# main.net
KiCad netlist of a schematic drawn in Altium Designer
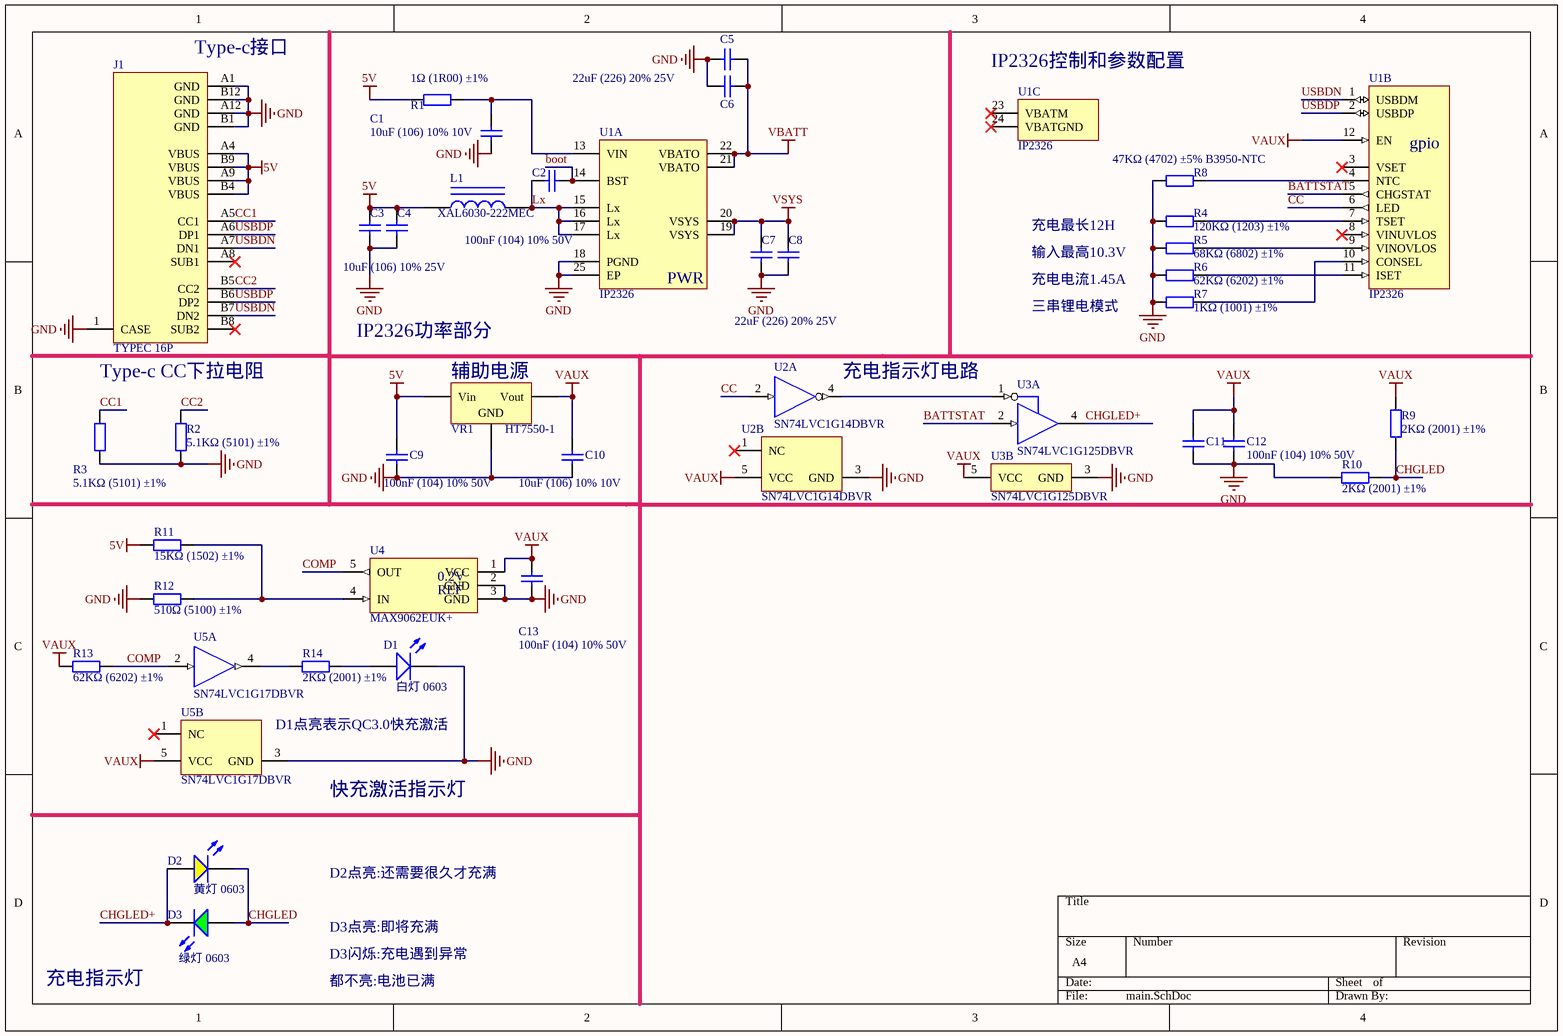
[diagram p0: main.SchDoc]

(export (version "E")
  (design (tool "Eeschema 10.0.6"))
  (components
    (comp (ref "C1")
      (value "10uF (106) 10% 10V")
      (footprint "0603_C")
      (description "贴片电容")
      (libsource (lib "Miscellaneous Devices LC") (part "0603 10uF (106) 10% 10V"))
    )
    (comp (ref "C2")
      (value "100nF (104) 10% 50V")
      (footprint "0603_C")
      (description "贴片电容")
      (libsource (lib "Miscellaneous Devices LC") (part "0603 100nF (104) 10% 50V"))
    )
    (comp (ref "C3")
      (value "10uF (106) 10% 25V")
      (footprint "0805_C")
      (description "贴片电容")
      (libsource (lib "Miscellaneous Devices LC") (part "0805 10uF (106) 10% 25V"))
    )
    (comp (ref "C4")
      (value "10uF (106) 10% 25V")
      (footprint "0805_C")
      (description "贴片电容")
      (libsource (lib "Miscellaneous Devices LC") (part "0805 10uF (106) 10% 25V"))
    )
    (comp (ref "C5")
      (value "22uF (226) 20% 25V")
      (footprint "0805_C")
      (description "贴片电容")
      (libsource (lib "Miscellaneous Devices LC") (part "0805 22uF (226) 20% 25V"))
    )
    (comp (ref "C6")
      (value "22uF (226) 20% 25V")
      (footprint "0805_C")
      (description "贴片电容")
      (libsource (lib "Miscellaneous Devices LC") (part "0805 22uF (226) 20% 25V"))
    )
    (comp (ref "C7")
      (value "22uF (226) 20% 25V")
      (footprint "0805_C")
      (description "贴片电容")
      (libsource (lib "Miscellaneous Devices LC") (part "0805 22uF (226) 20% 25V"))
    )
    (comp (ref "C8")
      (value "22uF (226) 20% 25V")
      (footprint "0805_C")
      (description "贴片电容")
      (libsource (lib "Miscellaneous Devices LC") (part "0805 22uF (226) 20% 25V"))
    )
    (comp (ref "C9")
      (value "100nF (104) 10% 50V")
      (footprint "0603_C")
      (description "贴片电容")
      (libsource (lib "Miscellaneous Devices LC") (part "0603 100nF (104) 10% 50V"))
    )
    (comp (ref "C10")
      (value "10uF (106) 10% 10V")
      (footprint "0603_C")
      (description "贴片电容")
      (libsource (lib "Miscellaneous Devices LC") (part "0603 10uF (106) 10% 10V"))
    )
    (comp (ref "C11")
      (value "100nF (104) 10% 50V")
      (footprint "0603_C")
      (description "贴片电容")
      (libsource (lib "Miscellaneous Devices LC") (part "0603 100nF (104) 10% 50V"))
    )
    (comp (ref "C12")
      (value "100nF (104) 10% 50V")
      (footprint "0603_C")
      (description "贴片电容")
      (libsource (lib "Miscellaneous Devices LC") (part "0603 100nF (104) 10% 50V"))
    )
    (comp (ref "C13")
      (value "100nF (104) 10% 50V")
      (footprint "0603_C")
      (description "贴片电容")
      (libsource (lib "Miscellaneous Devices LC") (part "0603 100nF (104) 10% 50V"))
    )
    (comp (ref "D1")
      (value "白灯 0603")
      (footprint "0603_LED_S1")
      (description "发光二极管")
      (libsource (lib "Miscellaneous Devices LC") (part "0603 白灯"))
    )
    (comp (ref "D2")
      (value "黄灯 0603")
      (footprint "0603_LED_S1")
      (description "发光二极管")
      (libsource (lib "Miscellaneous Devices LC") (part "0603 黄灯"))
    )
    (comp (ref "D3")
      (value "绿灯 0603")
      (footprint "0603_LED_S1")
      (description "发光二极管")
      (libsource (lib "Miscellaneous Devices LC") (part "0603 绿灯"))
    )
    (comp (ref "J1")
      (value "TYPEC 16P")
      (footprint "USB-C-SMD_KH-TYPE-C-16P")
      (description "16Pin TypeC立贴座子")
      (libsource (lib "custom") (part "KH-TYPEC-16P"))
    )
    (comp (ref "L1")
      (value "XAL6030-222MEC")
      (footprint "XAL6030-xxxME")
      (description "Magnetic-Core Inductor")
      (fields (field (name "PUBLISHER") "Altium Limited"))
      (libsource (lib "Miscellaneous Devices") (part "Inductor Iron"))
    )
    (comp (ref "R1")
      (value "1Ω (1R00) ±1%")
      (footprint "0603_R")
      (description "贴片电阻")
      (libsource (lib "Miscellaneous Devices LC") (part "0603 1Ω (1R00) 1%"))
    )
    (comp (ref "R2")
      (value "5.1KΩ (5101) ±1%")
      (footprint "0603_R")
      (description "贴片电阻")
      (libsource (lib "Miscellaneous Devices LC") (part "0603 5.1KΩ (5101) 1%"))
    )
    (comp (ref "R3")
      (value "5.1KΩ (5101) ±1%")
      (footprint "0603_R")
      (description "贴片电阻")
      (libsource (lib "Miscellaneous Devices LC") (part "0603 5.1KΩ (5101) 1%"))
    )
    (comp (ref "R4")
      (value "120KΩ (1203) ±1%")
      (footprint "0603_R")
      (description "贴片电阻")
      (libsource (lib "Miscellaneous Devices LC") (part "0603 120KΩ (1203) 1%"))
    )
    (comp (ref "R5")
      (value "68KΩ (6802) ±1%")
      (footprint "0603_R")
      (description "贴片电阻")
      (libsource (lib "Miscellaneous Devices LC") (part "0603 68KΩ (6802) 1%"))
    )
    (comp (ref "R6")
      (value "62KΩ (6202) ±1%")
      (footprint "0603_R")
      (description "贴片电阻")
      (libsource (lib "Miscellaneous Devices LC") (part "0603 62KΩ (6202) 1%"))
    )
    (comp (ref "R7")
      (value "1KΩ (1001) ±1%")
      (footprint "0603_R")
      (description "贴片电阻")
      (libsource (lib "Miscellaneous Devices LC") (part "0603 1KΩ (1001) 1%"))
    )
    (comp (ref "R8")
      (value "47KΩ (4702) ±5% B3950-NTC")
      (footprint "0603_R")
      (description "贴片NTC热敏电阻")
      (libsource (lib "Miscellaneous Devices LC") (part "0603 100KΩ (1003) 1%"))
    )
    (comp (ref "R9")
      (value "2KΩ (2001) ±1%")
      (footprint "0603_R")
      (description "贴片电阻")
      (libsource (lib "Miscellaneous Devices LC") (part "0603 2KΩ (2001) 1%"))
    )
    (comp (ref "R10")
      (value "2KΩ (2001) ±1%")
      (footprint "0603_R")
      (description "贴片电阻")
      (libsource (lib "") (part "0603 2KΩ (2001) 1%_1"))
    )
    (comp (ref "R11")
      (value "15KΩ (1502) ±1%")
      (footprint "0603_R")
      (description "贴片电阻")
      (libsource (lib "Miscellaneous Devices LC") (part "0603 15KΩ (1502) 1%"))
    )
    (comp (ref "R12")
      (value "510Ω (5100) ±1%")
      (footprint "0603_R")
      (description "贴片电阻")
      (libsource (lib "Miscellaneous Devices LC") (part "0603 510Ω (5100) 1%"))
    )
    (comp (ref "R13")
      (value "62KΩ (6202) ±1%")
      (footprint "0603_R")
      (description "贴片电阻")
      (libsource (lib "") (part "0603 62KΩ (6202) 1%_1"))
    )
    (comp (ref "R14")
      (value "2KΩ (2001) ±1%")
      (footprint "0603_R")
      (description "贴片电阻")
      (libsource (lib "") (part "0603 2KΩ (2001) 1%_2"))
    )
    (comp (ref "U1")
      (value "IP2326")
      (footprint "QFN50P400X400X80_HS-25M")
      (description "1.5A 2/3S Li-ION Battery charger")
      (libsource (lib "custom") (part "IP2326"))
    )
    (comp (ref "U2")
      (value "SN74LVC1G14DBVR")
      (footprint "DBV0005A_N")
      (description "Single Schmitt-Trigger Inverter, DBV0005A, LARGE T&R")
      (fields
        (field (name "GENERIC PART NUMBER") "SN74LVC1G14")
        (field (name "MANUFACTURER") "Texas Instruments")
      )
      (libsource (lib "TI_Logic_Little_Logic") (part "SN74LVC1G14DBVR"))
    )
    (comp (ref "U3")
      (value "SN74LVC1G125DBVR")
      (footprint "DBV0005A_N")
      (description "Single Bus Buffer Gate With 3-State Outputs, DBV0005A, LARGE T&R")
      (fields
        (field (name "GENERIC PART NUMBER") "SN74LVC1G125")
        (field (name "MANUFACTURER") "Texas Instruments")
      )
      (libsource (lib "TI_Logic_Little_Logic") (part "SN74LVC1G125DBVR"))
    )
    (comp (ref "U4")
      (value "MAX9062EUK+")
      (footprint "SOT95P245X110-5N")
      (description "tiny Comparator with 0.2V Ref OD Output")
      (libsource (lib "custom") (part "MAX9062"))
    )
    (comp (ref "U5")
      (value "SN74LVC1G17DBVR")
      (footprint "DBV0005A_N")
      (description "Single Schmitt-Trigger Buffer, DBV0005A, LARGE T&R")
      (fields
        (field (name "GENERIC PART NUMBER") "SN74LVC1G17")
        (field (name "MANUFACTURER") "Texas Instruments")
      )
      (libsource (lib "TI_Logic_Little_Logic") (part "SN74LVC1G17DBVR"))
    )
    (comp (ref "VR1")
      (value "HT7550-1")
      (footprint "SOT-89(SOT-89-3)")
      (description "低压差线性稳压(LDO)")
      (libsource (lib "Miscellaneous Devices LC") (part "SOT-89 HT7550-1"))
    )
  )
  (nets
    (net (code "1") (name "/BATTSTAT") (class "Default")
      (node (ref "U1") (pin "5") (pinfunction "CHGSTAT_5") (pintype "output"))
      (node (ref "U3") (pin "2") (pinfunction "A_2") (pintype "input"))
    )
    (net (code "2") (name "/CC") (class "Default")
      (node (ref "U1") (pin "6") (pinfunction "LED_6") (pintype "output"))
      (node (ref "U2") (pin "2") (pinfunction "A_2") (pintype "input"))
    )
    (net (code "3") (name "/CC1") (class "Default")
      (node (ref "J1") (pin "A5") (pinfunction "CC1_A5") (pintype "passive"))
      (node (ref "R3") (pin "2") (pinfunction "2_2") (pintype "passive"))
    )
    (net (code "4") (name "/CC2") (class "Default")
      (node (ref "J1") (pin "B5") (pinfunction "CC2_B5") (pintype "passive"))
      (node (ref "R2") (pin "2") (pinfunction "2_2") (pintype "passive"))
    )
    (net (code "5") (name "/CHGLED") (class "Default")
      (node (ref "D2") (pin "K") (pinfunction "K_K") (pintype "passive"))
      (node (ref "D3") (pin "A") (pinfunction "A_A") (pintype "passive"))
      (node (ref "R10") (pin "1") (pinfunction "1_1") (pintype "passive"))
      (node (ref "R9") (pin "1") (pinfunction "1_1") (pintype "passive"))
    )
    (net (code "6") (name "/CHGLED+") (class "Default")
      (node (ref "D2") (pin "A") (pinfunction "A_A") (pintype "passive"))
      (node (ref "D3") (pin "K") (pinfunction "K_K") (pintype "passive"))
      (node (ref "U3") (pin "4") (pinfunction "Y_4") (pintype "tri_state"))
    )
    (net (code "7") (name "/COMP") (class "Default")
      (node (ref "R13") (pin "1") (pinfunction "1_1") (pintype "passive"))
      (node (ref "U4") (pin "5") (pinfunction "OUT_5") (pintype "output"))
      (node (ref "U5") (pin "2") (pinfunction "A_2") (pintype "input"))
    )
    (net (code "8") (name "/Lx") (class "Default")
      (node (ref "C2") (pin "1") (pinfunction "1_1") (pintype "passive"))
      (node (ref "L1") (pin "2") (pinfunction "2_2") (pintype "passive"))
      (node (ref "U1") (pin "15") (pinfunction "Lx_15") (pintype "power_in"))
      (node (ref "U1") (pin "16") (pinfunction "Lx_16") (pintype "power_in"))
      (node (ref "U1") (pin "17") (pinfunction "Lx_17") (pintype "power_in"))
    )
    (net (code "9") (name "/USBDN") (class "Default")
      (node (ref "J1") (pin "A7") (pinfunction "DN1_A7") (pintype "passive"))
      (node (ref "J1") (pin "B7") (pinfunction "DN2_B7") (pintype "passive"))
      (node (ref "U1") (pin "1") (pinfunction "USBDM_1") (pintype "bidirectional"))
    )
    (net (code "10") (name "/USBDP") (class "Default")
      (node (ref "J1") (pin "A6") (pinfunction "DP1_A6") (pintype "passive"))
      (node (ref "J1") (pin "B6") (pinfunction "DP2_B6") (pintype "passive"))
      (node (ref "U1") (pin "2") (pinfunction "USBDP_2") (pintype "bidirectional"))
    )
    (net (code "11") (name "/boot") (class "Default")
      (node (ref "C2") (pin "2") (pinfunction "2_2") (pintype "passive"))
      (node (ref "U1") (pin "14") (pinfunction "BST_14") (pintype "power_in"))
    )
    (net (code "12") (name "5V") (class "Default")
      (node (ref "C3") (pin "2") (pinfunction "2_2") (pintype "passive"))
      (node (ref "C4") (pin "2") (pinfunction "2_2") (pintype "passive"))
      (node (ref "C9") (pin "2") (pinfunction "2_2") (pintype "passive"))
      (node (ref "J1") (pin "A4") (pinfunction "VBUS_A4") (pintype "passive"))
      (node (ref "J1") (pin "A9") (pinfunction "VBUS_A9") (pintype "passive"))
      (node (ref "J1") (pin "B4") (pinfunction "VBUS_B4") (pintype "passive"))
      (node (ref "J1") (pin "B9") (pinfunction "VBUS_B9") (pintype "passive"))
      (node (ref "L1") (pin "1") (pinfunction "1_1") (pintype "passive"))
      (node (ref "R1") (pin "1") (pinfunction "1_1") (pintype "passive"))
      (node (ref "R11") (pin "1") (pinfunction "1_1") (pintype "passive"))
      (node (ref "VR1") (pin "2") (pinfunction "Vin_2") (pintype "passive"))
    )
    (net (code "13") (name "GND") (class "Default")
      (node (ref "C1") (pin "1") (pinfunction "1_1") (pintype "passive"))
      (node (ref "C10") (pin "1") (pinfunction "1_1") (pintype "passive"))
      (node (ref "C11") (pin "1") (pinfunction "1_1") (pintype "passive"))
      (node (ref "C12") (pin "1") (pinfunction "1_1") (pintype "passive"))
      (node (ref "C13") (pin "1") (pinfunction "1_1") (pintype "passive"))
      (node (ref "C3") (pin "1") (pinfunction "1_1") (pintype "passive"))
      (node (ref "C4") (pin "1") (pinfunction "1_1") (pintype "passive"))
      (node (ref "C5") (pin "2") (pinfunction "2_2") (pintype "passive"))
      (node (ref "C6") (pin "1") (pinfunction "1_1") (pintype "passive"))
      (node (ref "C7") (pin "1") (pinfunction "1_1") (pintype "passive"))
      (node (ref "C8") (pin "1") (pinfunction "1_1") (pintype "passive"))
      (node (ref "C9") (pin "1") (pinfunction "1_1") (pintype "passive"))
      (node (ref "D1") (pin "K") (pinfunction "K_K") (pintype "passive"))
      (node (ref "J1") (pin "1") (pinfunction "CASE_1") (pintype "passive"))
      (node (ref "J1") (pin "A1") (pinfunction "GND_A1") (pintype "passive"))
      (node (ref "J1") (pin "A12") (pinfunction "GND_A12") (pintype "passive"))
      (node (ref "J1") (pin "B1") (pinfunction "GND_B1") (pintype "passive"))
      (node (ref "J1") (pin "B12") (pinfunction "GND_B12") (pintype "passive"))
      (node (ref "R10") (pin "2") (pinfunction "2_2") (pintype "passive"))
      (node (ref "R12") (pin "1") (pinfunction "1_1") (pintype "passive"))
      (node (ref "R2") (pin "1") (pinfunction "1_1") (pintype "passive"))
      (node (ref "R3") (pin "1") (pinfunction "1_1") (pintype "passive"))
      (node (ref "R4") (pin "1") (pinfunction "1_1") (pintype "passive"))
      (node (ref "R5") (pin "1") (pinfunction "1_1") (pintype "passive"))
      (node (ref "R6") (pin "1") (pinfunction "1_1") (pintype "passive"))
      (node (ref "R7") (pin "1") (pinfunction "1_1") (pintype "passive"))
      (node (ref "R8") (pin "1") (pinfunction "1_1") (pintype "passive"))
      (node (ref "U1") (pin "18") (pinfunction "PGND_18") (pintype "power_in"))
      (node (ref "U1") (pin "25") (pinfunction "EP_25") (pintype "power_in"))
      (node (ref "U2") (pin "3") (pinfunction "GND_3") (pintype "power_in"))
      (node (ref "U3") (pin "3") (pinfunction "GND_3") (pintype "power_in"))
      (node (ref "U4") (pin "2") (pinfunction "GND_2") (pintype "power_in"))
      (node (ref "U4") (pin "3") (pinfunction "GND_3") (pintype "power_in"))
      (node (ref "U5") (pin "3") (pinfunction "GND_3") (pintype "power_in"))
      (node (ref "VR1") (pin "1") (pinfunction "GND_1") (pintype "passive"))
    )
    (net (code "14") (name "Net-(D1-PadA)") (class "Default")
      (node (ref "D1") (pin "A") (pinfunction "A_A") (pintype "passive"))
      (node (ref "R14") (pin "2") (pinfunction "2_2") (pintype "passive"))
    )
    (net (code "15") (name "Net-(U1A-VIN)") (class "Default")
      (node (ref "C1") (pin "2") (pinfunction "2_2") (pintype "passive"))
      (node (ref "R1") (pin "2") (pinfunction "2_2") (pintype "passive"))
      (node (ref "U1") (pin "13") (pinfunction "VIN_13") (pintype "power_in"))
    )
    (net (code "16") (name "Net-(U1B-CONSEL)") (class "Default")
      (node (ref "R7") (pin "2") (pinfunction "2_2") (pintype "passive"))
      (node (ref "U1") (pin "10") (pinfunction "CONSEL_10") (pintype "input"))
    )
    (net (code "17") (name "Net-(U1B-ISET)") (class "Default")
      (node (ref "R6") (pin "2") (pinfunction "2_2") (pintype "passive"))
      (node (ref "U1") (pin "11") (pinfunction "ISET_11") (pintype "input"))
    )
    (net (code "18") (name "Net-(U1B-NTC)") (class "Default")
      (node (ref "R8") (pin "2") (pinfunction "2_2") (pintype "passive"))
      (node (ref "U1") (pin "4") (pinfunction "NTC_4") (pintype "passive"))
    )
    (net (code "19") (name "Net-(U1B-TSET)") (class "Default")
      (node (ref "R4") (pin "2") (pinfunction "2_2") (pintype "passive"))
      (node (ref "U1") (pin "7") (pinfunction "TSET_7") (pintype "input"))
    )
    (net (code "20") (name "Net-(U1B-VINOVLOS)") (class "Default")
      (node (ref "R5") (pin "2") (pinfunction "2_2") (pintype "passive"))
      (node (ref "U1") (pin "9") (pinfunction "VINOVLOS_9") (pintype "input"))
    )
    (net (code "21") (name "Net-(U2A-Y)") (class "Default")
      (node (ref "U2") (pin "4") (pinfunction "Y_4") (pintype "output"))
      (node (ref "U3") (pin "1") (pinfunction "~{OE}_1") (pintype "input"))
    )
    (net (code "22") (name "Net-(U4-IN)") (class "Default")
      (node (ref "R11") (pin "2") (pinfunction "2_2") (pintype "passive"))
      (node (ref "R12") (pin "2") (pinfunction "2_2") (pintype "passive"))
      (node (ref "U4") (pin "4") (pinfunction "IN_4") (pintype "input"))
    )
    (net (code "23") (name "Net-(U5A-Y)") (class "Default")
      (node (ref "R14") (pin "1") (pinfunction "1_1") (pintype "passive"))
      (node (ref "U5") (pin "4") (pinfunction "Y_4") (pintype "output"))
    )
    (net (code "24") (name "VAUX") (class "Default")
      (node (ref "C10") (pin "2") (pinfunction "2_2") (pintype "passive"))
      (node (ref "C11") (pin "2") (pinfunction "2_2") (pintype "passive"))
      (node (ref "C12") (pin "2") (pinfunction "2_2") (pintype "passive"))
      (node (ref "C13") (pin "2") (pinfunction "2_2") (pintype "passive"))
      (node (ref "R13") (pin "2") (pinfunction "2_2") (pintype "passive"))
      (node (ref "R9") (pin "2") (pinfunction "2_2") (pintype "passive"))
      (node (ref "U1") (pin "12") (pinfunction "EN_12") (pintype "input"))
      (node (ref "U2") (pin "5") (pinfunction "VCC_5") (pintype "power_in"))
      (node (ref "U3") (pin "5") (pinfunction "VCC_5") (pintype "power_in"))
      (node (ref "U4") (pin "1") (pinfunction "VCC_1") (pintype "power_in"))
      (node (ref "U5") (pin "5") (pinfunction "VCC_5") (pintype "power_in"))
      (node (ref "VR1") (pin "3") (pinfunction "Vout_3") (pintype "passive"))
    )
    (net (code "25") (name "VBATT") (class "Default")
      (node (ref "C5") (pin "1") (pinfunction "1_1") (pintype "passive"))
      (node (ref "C6") (pin "2") (pinfunction "2_2") (pintype "passive"))
      (node (ref "U1") (pin "21") (pinfunction "VBATO_21") (pintype "power_in"))
      (node (ref "U1") (pin "22") (pinfunction "VBATO_22") (pintype "power_in"))
    )
    (net (code "26") (name "VSYS") (class "Default")
      (node (ref "C7") (pin "2") (pinfunction "2_2") (pintype "passive"))
      (node (ref "C8") (pin "2") (pinfunction "2_2") (pintype "passive"))
      (node (ref "U1") (pin "19") (pinfunction "VSYS_19") (pintype "power_in"))
      (node (ref "U1") (pin "20") (pinfunction "VSYS_20") (pintype "power_in"))
    )
    (net (code "27") (name "unconnected-(J1-SUB1-PadA8)") (class "Default")
      (node (ref "J1") (pin "A8") (pinfunction "SUB1_A8") (pintype "passive+no_connect"))
    )
    (net (code "28") (name "unconnected-(J1-SUB2-PadB8)") (class "Default")
      (node (ref "J1") (pin "B8") (pinfunction "SUB2_B8") (pintype "passive+no_connect"))
    )
    (net (code "29") (name "unconnected-(U1B-VINUVLOS-Pad8)") (class "Default")
      (node (ref "U1") (pin "8") (pinfunction "VINUVLOS_8") (pintype "input+no_connect"))
    )
    (net (code "30") (name "unconnected-(U1B-VSET-Pad3)") (class "Default")
      (node (ref "U1") (pin "3") (pinfunction "VSET_3") (pintype "passive+no_connect"))
    )
    (net (code "31") (name "unconnected-(U1C-VBATGND-Pad24)") (class "Default")
      (node (ref "U1") (pin "24") (pinfunction "VBATGND_24") (pintype "passive+no_connect"))
    )
    (net (code "32") (name "unconnected-(U1C-VBATM-Pad23)") (class "Default")
      (node (ref "U1") (pin "23") (pinfunction "VBATM_23") (pintype "passive+no_connect"))
    )
    (net (code "33") (name "unconnected-(U2B-NC-Pad1)") (class "Default")
      (node (ref "U2") (pin "1") (pinfunction "NC_1") (pintype "passive+no_connect"))
    )
    (net (code "34") (name "unconnected-(U5B-NC-Pad1)") (class "Default")
      (node (ref "U5") (pin "1") (pinfunction "NC_1") (pintype "passive+no_connect"))
    )
  )
)
